# LevelShifter.net
KiCad netlist of a schematic drawn in Altium Designer
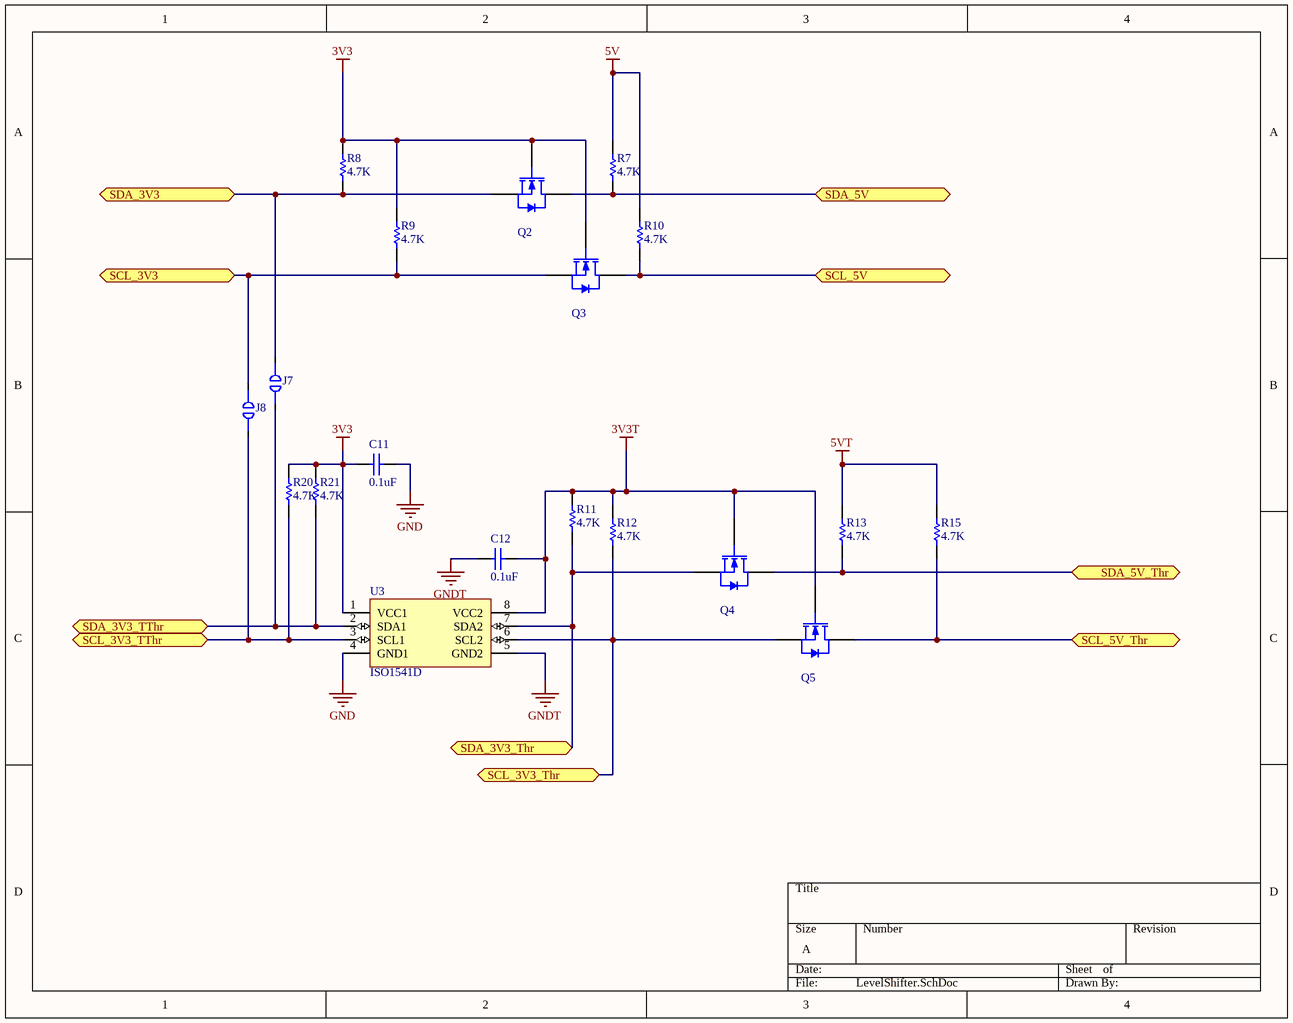
[diagram p0: LevelShifter.SchDoc]

(export (version "E")
  (design (tool "Eeschema 10.0.6"))
  (components
    (comp (ref "C11")
      (value "0.1uF")
      (footprint "CAPC1608X97X38NL12T08")
      (description "CAP CER 0.1UF 25V X7R 0603")
      (fields (field (name "MANUFACTURER") "Vitramon") (field (name "PART NUMBER") "VJ0603Y-104KXXAC"))
      (libsource (lib "Main") (part "VJ0603Y104KXXAC"))
    )
    (comp (ref "C12")
      (value "0.1uF")
      (footprint "CAPC1608X97X38NL12T08")
      (description "CAP CER 0.1UF 25V X7R 0603")
      (fields (field (name "MANUFACTURER") "Vitramon") (field (name "PART NUMBER") "VJ0603Y-104KXXAC"))
      (libsource (lib "Main") (part "VJ0603Y104KXXAC"))
    )
    (comp (ref "J7")
      (value "Solder Jumper")
      (footprint "SolderJumper")
      (description "Simple Jumper")
      (libsource (lib "Main") (part "Solder Jumper"))
    )
    (comp (ref "J8")
      (value "Solder Jumper")
      (footprint "SolderJumper")
      (description "Simple Jumper")
      (libsource (lib "Main") (part "Solder Jumper"))
    )
    (comp (ref "Q2")
      (value "MOSFET N-CH")
      (footprint "ONSC-SOT-23-3-318-08_V")
      (description "MOSFET N-CH 50V 200MA SOT-23")
      (libsource (lib "Main") (part "BSS138LT1G"))
    )
    (comp (ref "Q3")
      (value "MOSFET N-CH")
      (footprint "ONSC-SOT-23-3-318-08_V")
      (description "MOSFET N-CH 50V 200MA SOT-23")
      (libsource (lib "Main") (part "BSS138LT1G"))
    )
    (comp (ref "Q4")
      (value "MOSFET N-CH")
      (footprint "ONSC-SOT-23-3-318-08_V")
      (description "MOSFET N-CH 50V 200MA SOT-23")
      (libsource (lib "Main") (part "BSS138LT1G"))
    )
    (comp (ref "Q5")
      (value "MOSFET N-CH")
      (footprint "ONSC-SOT-23-3-318-08_V")
      (description "MOSFET N-CH 50V 200MA SOT-23")
      (libsource (lib "Main") (part "BSS138LT1G"))
    )
    (comp (ref "R7")
      (value "4.7K")
      (footprint "RESC1609X55X30NL10T20")
      (description "RES 4.7K  OHM 0.1% 1/8W 0603")
      (fields (field (name "TOLERANCE") "0.1%"))
      (libsource (lib "Main") (part "TNPW06034K70BEEN"))
    )
    (comp (ref "R8")
      (value "4.7K")
      (footprint "RESC1609X55X30NL10T20")
      (description "RES 4.7K  OHM 0.1% 1/8W 0603")
      (fields (field (name "TOLERANCE") "0.1%"))
      (libsource (lib "Main") (part "TNPW06034K70BEEN"))
    )
    (comp (ref "R9")
      (value "4.7K")
      (footprint "RESC1609X55X30NL10T20")
      (description "RES 4.7K  OHM 0.1% 1/8W 0603")
      (fields (field (name "TOLERANCE") "0.1%"))
      (libsource (lib "Main") (part "TNPW06034K70BEEN"))
    )
    (comp (ref "R10")
      (value "4.7K")
      (footprint "RESC1609X55X30NL10T20")
      (description "RES 4.7K  OHM 0.1% 1/8W 0603")
      (fields (field (name "TOLERANCE") "0.1%"))
      (libsource (lib "Main") (part "TNPW06034K70BEEN"))
    )
    (comp (ref "R11")
      (value "4.7K")
      (footprint "RESC1609X55X30NL10T20")
      (description "RES 4.7K  OHM 0.1% 1/8W 0603")
      (fields (field (name "TOLERANCE") "0.1%"))
      (libsource (lib "Main") (part "TNPW06034K70BEEN"))
    )
    (comp (ref "R12")
      (value "4.7K")
      (footprint "RESC1609X55X30NL10T20")
      (description "RES 4.7K  OHM 0.1% 1/8W 0603")
      (fields (field (name "TOLERANCE") "0.1%"))
      (libsource (lib "Main") (part "TNPW06034K70BEEN"))
    )
    (comp (ref "R13")
      (value "4.7K")
      (footprint "RESC1609X55X30NL10T20")
      (description "RES 4.7K  OHM 0.1% 1/8W 0603")
      (fields (field (name "TOLERANCE") "0.1%"))
      (libsource (lib "Main") (part "TNPW06034K70BEEN"))
    )
    (comp (ref "R15")
      (value "4.7K")
      (footprint "RESC1609X55X30NL10T20")
      (description "RES 4.7K  OHM 0.1% 1/8W 0603")
      (fields (field (name "TOLERANCE") "0.1%"))
      (libsource (lib "Main") (part "TNPW06034K70BEEN"))
    )
    (comp (ref "R20")
      (value "4.7K")
      (footprint "RESC1609X55X30NL10T20")
      (description "RES 4.7K  OHM 0.1% 1/8W 0603")
      (fields (field (name "TOLERANCE") "0.1%"))
      (libsource (lib "Main") (part "TNPW06034K70BEEN"))
    )
    (comp (ref "R21")
      (value "4.7K")
      (footprint "RESC1609X55X30NL10T20")
      (description "RES 4.7K  OHM 0.1% 1/8W 0603")
      (fields (field (name "TOLERANCE") "0.1%"))
      (libsource (lib "Main") (part "TNPW06034K70BEEN"))
    )
    (comp (ref "U3")
      (value "ISO1541D")
      (footprint "ISO1541D")
      (description "I²C Digital Isolator 2500Vrms 2 Channel 1Mbps 25kV/µs CMTI 8-SOIC (0.154\", 3.90mm Width)")
      (fields (field (name "MANUFACTURER") "Texas Instruments"))
      (libsource (lib "Main") (part "ISO1541D"))
    )
  )
  (nets
    (net (code "1") (name "/SCL_3V3") (class "Default")
      (node (ref "J8") (pin "2") (pinfunction "2_2") (pintype "passive"))
      (node (ref "Q3") (pin "2") (pinfunction "S_2") (pintype "passive"))
      (node (ref "R9") (pin "1") (pinfunction "1_1") (pintype "passive"))
    )
    (net (code "2") (name "/SCL_3V3_TThr") (class "Default")
      (node (ref "J8") (pin "1") (pinfunction "1_1") (pintype "passive"))
      (node (ref "R20") (pin "1") (pinfunction "1_1") (pintype "passive"))
      (node (ref "U3") (pin "3") (pinfunction "SCL1_3") (pintype "bidirectional"))
    )
    (net (code "3") (name "/SCL_3V3_Thr") (class "Default")
      (node (ref "Q5") (pin "2") (pinfunction "S_2") (pintype "passive"))
      (node (ref "R12") (pin "1") (pinfunction "1_1") (pintype "passive"))
      (node (ref "U3") (pin "6") (pinfunction "SCL2_6") (pintype "bidirectional"))
    )
    (net (code "4") (name "/SCL_5V") (class "Default")
      (node (ref "Q3") (pin "3") (pinfunction "D_3") (pintype "passive"))
      (node (ref "R10") (pin "1") (pinfunction "1_1") (pintype "passive"))
    )
    (net (code "5") (name "/SCL_5V_Thr") (class "Default")
      (node (ref "Q5") (pin "3") (pinfunction "D_3") (pintype "passive"))
      (node (ref "R15") (pin "1") (pinfunction "1_1") (pintype "passive"))
    )
    (net (code "6") (name "/SDA_3V3") (class "Default")
      (node (ref "J7") (pin "2") (pinfunction "2_2") (pintype "passive"))
      (node (ref "Q2") (pin "2") (pinfunction "S_2") (pintype "passive"))
      (node (ref "R8") (pin "1") (pinfunction "1_1") (pintype "passive"))
    )
    (net (code "7") (name "/SDA_3V3_TThr") (class "Default")
      (node (ref "J7") (pin "1") (pinfunction "1_1") (pintype "passive"))
      (node (ref "R21") (pin "1") (pinfunction "1_1") (pintype "passive"))
      (node (ref "U3") (pin "2") (pinfunction "SDA1_2") (pintype "bidirectional"))
    )
    (net (code "8") (name "/SDA_3V3_Thr") (class "Default")
      (node (ref "Q4") (pin "2") (pinfunction "S_2") (pintype "passive"))
      (node (ref "R11") (pin "1") (pinfunction "1_1") (pintype "passive"))
      (node (ref "U3") (pin "7") (pinfunction "SDA2_7") (pintype "bidirectional"))
    )
    (net (code "9") (name "/SDA_5V") (class "Default")
      (node (ref "Q2") (pin "3") (pinfunction "D_3") (pintype "passive"))
      (node (ref "R7") (pin "1") (pinfunction "1_1") (pintype "passive"))
    )
    (net (code "10") (name "/SDA_5V_Thr") (class "Default")
      (node (ref "Q4") (pin "3") (pinfunction "D_3") (pintype "passive"))
      (node (ref "R13") (pin "1") (pinfunction "1_1") (pintype "passive"))
    )
    (net (code "11") (name "3V3") (class "Default")
      (node (ref "C11") (pin "2") (pinfunction "2_2") (pintype "passive"))
      (node (ref "Q2") (pin "1") (pinfunction "G_1") (pintype "passive"))
      (node (ref "Q3") (pin "1") (pinfunction "G_1") (pintype "passive"))
      (node (ref "R20") (pin "2") (pinfunction "2_2") (pintype "passive"))
      (node (ref "R21") (pin "2") (pinfunction "2_2") (pintype "passive"))
      (node (ref "R8") (pin "2") (pinfunction "2_2") (pintype "passive"))
      (node (ref "R9") (pin "2") (pinfunction "2_2") (pintype "passive"))
      (node (ref "U3") (pin "1") (pinfunction "VCC1_1") (pintype "power_in"))
    )
    (net (code "12") (name "3V3T") (class "Default")
      (node (ref "C12") (pin "1") (pinfunction "1_1") (pintype "passive"))
      (node (ref "Q4") (pin "1") (pinfunction "G_1") (pintype "passive"))
      (node (ref "Q5") (pin "1") (pinfunction "G_1") (pintype "passive"))
      (node (ref "R11") (pin "2") (pinfunction "2_2") (pintype "passive"))
      (node (ref "R12") (pin "2") (pinfunction "2_2") (pintype "passive"))
      (node (ref "U3") (pin "8") (pinfunction "VCC2_8") (pintype "power_in"))
    )
    (net (code "13") (name "5V") (class "Default")
      (node (ref "R10") (pin "2") (pinfunction "2_2") (pintype "passive"))
      (node (ref "R7") (pin "2") (pinfunction "2_2") (pintype "passive"))
    )
    (net (code "14") (name "5VT") (class "Default")
      (node (ref "R13") (pin "2") (pinfunction "2_2") (pintype "passive"))
      (node (ref "R15") (pin "2") (pinfunction "2_2") (pintype "passive"))
    )
    (net (code "15") (name "GND") (class "Default")
      (node (ref "C11") (pin "1") (pinfunction "1_1") (pintype "passive"))
      (node (ref "U3") (pin "4") (pinfunction "GND1_4") (pintype "power_in"))
    )
    (net (code "16") (name "GNDT") (class "Default")
      (node (ref "C12") (pin "2") (pinfunction "2_2") (pintype "passive"))
      (node (ref "U3") (pin "5") (pinfunction "GND2_5") (pintype "power_in"))
    )
  )
)
